# MSXII_DC-DC_Converter.net
KiCad netlist of a schematic drawn in Altium Designer
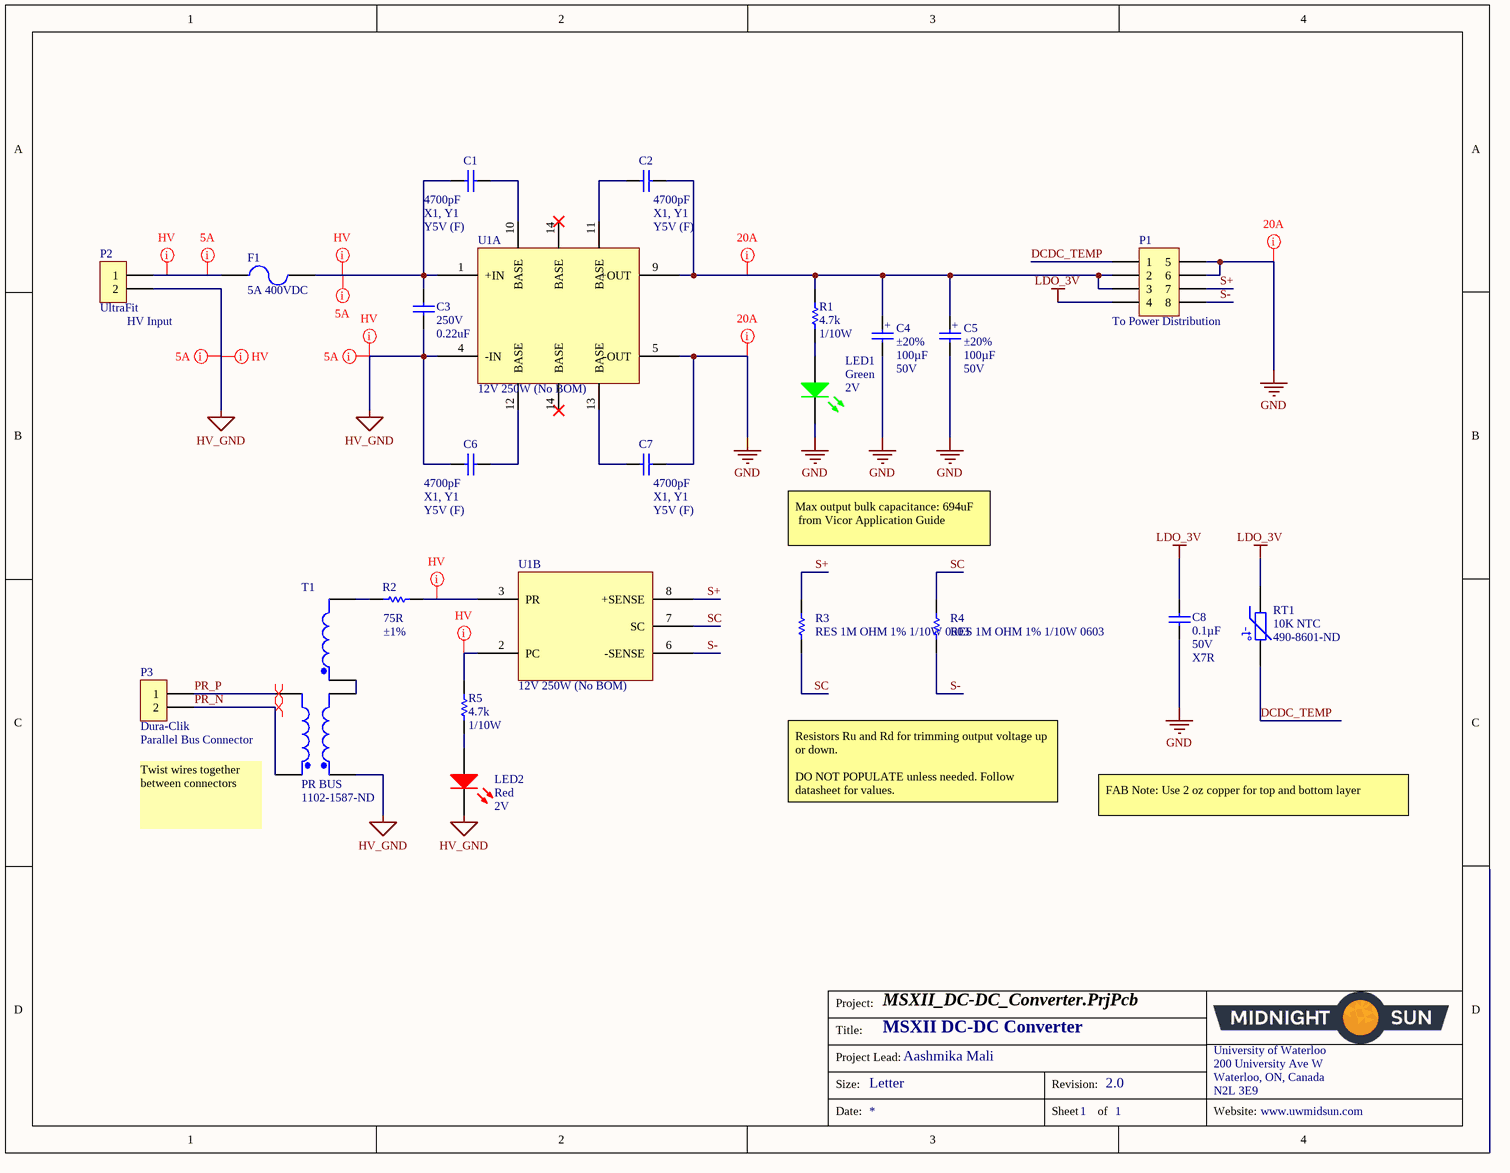
[diagram p0: MSXII_DC-DC_Converter.SchDoc]

(export (version "E")
  (design (tool "Eeschema 10.0.6"))
  (components
    (comp (ref "C1")
      (value "4700pF")
      (footprint "CAP 4700PF 400VAC Y5V RADIAL")
      (description "4700pF ±20% 400VAC Ceramic Capacitor Y5V (F) Radial, Disc")
      (fields
        (field (name "MANUFACTURER") "KEMET")
        (field (name "MANUFACTURER PART NUMBER") "C951U472MVVDBA7317")
        (field (name "TEMPERATURE COEFFICIENT") "Y5V (F)")
        (field (name "RATINGS") "X1, Y1")
      )
      (libsource (lib "Schematic Diagrams") (part "CAP CER 4700PF 400VAC Y5V RADIAL"))
    )
    (comp (ref "C2")
      (value "4700pF")
      (footprint "CAP 4700PF 400VAC Y5V RADIAL")
      (description "4700pF ±20% 400VAC Ceramic Capacitor Y5V (F) Radial, Disc")
      (fields
        (field (name "MANUFACTURER") "KEMET")
        (field (name "MANUFACTURER PART NUMBER") "C951U472MVVDBA7317")
        (field (name "TEMPERATURE COEFFICIENT") "Y5V (F)")
        (field (name "RATINGS") "X1, Y1")
      )
      (libsource (lib "Schematic Diagrams") (part "CAP CER 4700PF 400VAC Y5V RADIAL"))
    )
    (comp (ref "C3")
      (value "0.22uF")
      (footprint "CAP FILM 0.22UF 5% 250VDC RADIAL")
      (fields
        (field (name "MANUFACTURER") "KEMET")
        (field (name "MANUFACTURER PART NUMBER") "R82IC3220AA60J")
        (field (name "TOLERANCE") "±5%")
        (field (name "VOLTAGE RATING - DC") "250V")
      )
      (libsource (lib "Schematic Diagrams") (part "CAP FILM 0.22UF 5% 250VDC RADIAL"))
    )
    (comp (ref "C4")
      (value "CAP ALUM 100UF 20% 50V RADIAL")
      (footprint "CAP ALUM 100UF 50V")
      (description "100µF 50V Aluminum Capacitors Radial, Can 74 mOhm @ 100kHz 3000 Hrs @ 105°C")
      (fields
        (field (name "TOLERANCE") "±20%")
        (field (name "CAPACITANCE") "100µF")
        (field (name "VOLTAGE RATING") "50V")
      )
      (libsource (lib "Schematic Diagrams") (part "CAP ALUM 100UF 20% 50V RADIAL"))
    )
    (comp (ref "C5")
      (value "CAP ALUM 100UF 20% 50V RADIAL")
      (footprint "CAP ALUM 100UF 50V")
      (description "100µF 50V Aluminum Capacitors Radial, Can 74 mOhm @ 100kHz 3000 Hrs @ 105°C")
      (fields
        (field (name "TOLERANCE") "±20%")
        (field (name "CAPACITANCE") "100µF")
        (field (name "VOLTAGE RATING") "50V")
      )
      (libsource (lib "Schematic Diagrams") (part "CAP ALUM 100UF 20% 50V RADIAL"))
    )
    (comp (ref "C6")
      (value "4700pF")
      (footprint "CAP 4700PF 400VAC Y5V RADIAL")
      (description "4700pF ±20% 400VAC Ceramic Capacitor Y5V (F) Radial, Disc")
      (fields
        (field (name "MANUFACTURER") "KEMET")
        (field (name "MANUFACTURER PART NUMBER") "C951U472MVVDBA7317")
        (field (name "TEMPERATURE COEFFICIENT") "Y5V (F)")
        (field (name "RATINGS") "X1, Y1")
      )
      (libsource (lib "Schematic Diagrams") (part "CAP CER 4700PF 400VAC Y5V RADIAL"))
    )
    (comp (ref "C7")
      (value "4700pF")
      (footprint "CAP 4700PF 400VAC Y5V RADIAL")
      (description "4700pF ±20% 400VAC Ceramic Capacitor Y5V (F) Radial, Disc")
      (fields
        (field (name "MANUFACTURER") "KEMET")
        (field (name "MANUFACTURER PART NUMBER") "C951U472MVVDBA7317")
        (field (name "TEMPERATURE COEFFICIENT") "Y5V (F)")
        (field (name "RATINGS") "X1, Y1")
      )
      (libsource (lib "Schematic Diagrams") (part "CAP CER 4700PF 400VAC Y5V RADIAL"))
    )
    (comp (ref "C8")
      (value "CAP CER 0.1UF 50V 10% X7R 0603")
      (footprint "CAP, 0603")
      (description "0.10µF ±10% 50V Ceramic Capacitor X7R 0603 (1608 Metric)")
      (fields
        (field (name "TOLERANCE") "±10%")
        (field (name "CAPACITANCE") "0.1µF")
        (field (name "VOLTAGE") "50V")
        (field (name "TEMPERATURE COEFFICIENT") "X7R")
      )
      (libsource (lib "Schematic Diagrams") (part "CAP CER 0.1UF 50V 10% X7R 0603"))
    )
    (comp (ref "F1")
      (value "5A 400VDC")
      (footprint "FUSE 5A 400VDC RADIAL")
      (description "FUSE BOARD MNT 5A 125VAC/400VDC")
      (fields (field (name "MANUFACTURER") "Eaton") (field (name "MANUFACTURER PART NUMBER") "BK/PCE-5-R"))
      (libsource (lib "Schematic Diagrams") (part "FUSE 5A 125VAC/400VDC RADIAL"))
    )
    (comp (ref "LED1")
      (value "LED GREEN CLEAR 2V 0603")
      (footprint "LED_0603")
      (description "Green 572nm LED Indication - Discrete 2V 0603 (1608 Metric)")
      (fields
        (field (name "MANUFACTURER") "Wurth Electronics Inc.")
        (field (name "MANUFACTURER PART NUMBER") "150060VS75000")
        (field (name "COLOR") "Green")
        (field (name "VOLTAGE - FORWARD (VF) (TYP)") "2V")
      )
      (libsource (lib "Schematic Diagrams") (part "LED GREEN CLEAR 2V 0603"))
    )
    (comp (ref "LED2")
      (value "LED RED CLEAR 2V 0603")
      (footprint "LED_0603")
      (description "Red 631nm LED Indication - Discrete 2V 0603 (1608 Metric)")
      (fields
        (field (name "MANUFACTURER") "Wurth Electronics Inc.")
        (field (name "MANUFACTURER PART NUMBER") "150060RS75000")
        (field (name "COLOR") "Red")
        (field (name "VOLTAGE - FORWARD (VF) (TYP)") "2V")
      )
      (libsource (lib "Schematic Diagrams") (part "LED RED CLEAR 2V 0603"))
    )
    (comp (ref "P1")
      (value "CONN 8POS ULTRA-FIT 0.138\"")
      (footprint "CONN, 8POS ULTRA-FIT")
      (description "8 Positions Header Connector 0.138\" (3.50mm) Through Hole Tin")
      (fields
        (field (name "MANUFACTURER") "Molex, LLC")
        (field (name "MANUFACTURER PART NUMBER") "1722991108")
      )
      (libsource (lib "Schematic Diagrams") (part "CONN 8POS ULTRA-FIT 0.138{dblquote}"))
    )
    (comp (ref "P2")
      (value "CONN 2POS ULTRA-FIT 0.138\"")
      (footprint "CONN, 2POS ULTRA-FIT")
      (description "2 Positions Header, Shrouded Connector 0.138\" (3.50mm) Through Hole Gold")
      (fields (field (name "VOLTAGE") "400V") (field (name "SERIES") "UltraFit"))
      (libsource (lib "Schematic Diagrams") (part "CONN 2POS ULTRA-FIT 0.138{dblquote}"))
    )
    (comp (ref "P3")
      (value "Dura-Clik")
      (footprint "CONN, 2POS Dura-Click Vertical")
      (description "2 Positions Header, Shrouded Connector 0.079\" (2.00mm) Surface Mount, Vertical Tin")
      (fields
        (field (name "MANUFACTURER") "Molex, LLC")
        (field (name "MANUFACTURER PART NUMBER") "5600200220")
      )
      (libsource (lib "Schematic Diagrams") (part "CONN 2POS DURA-CLIK 0.079{dblquote} VERT"))
    )
    (comp (ref "R1")
      (value "RES 4.7K OHM 1% 1/10W 0603")
      (footprint "RES, 0603")
      (description "4.7k Ohm ±1% 0.1W, 1/10W Chip Resistor 0603 (1608 Metric) Moisture Resistant Thick Film")
      (fields
        (field (name "TOLERANCE") "±1%")
        (field (name "RESISTANCE (OHMS)") "4.7k")
        (field (name "POWER (WATTS)") "1/10W")
      )
      (libsource (lib "Schematic Diagrams") (part "RES 4.7K OHM 1% 1/10W 0603"))
    )
    (comp (ref "R2")
      (value "75R")
      (footprint "RES, 0603")
      (fields
        (field (name "MANUFACTURER") "Yageo")
        (field (name "MANUFACTURER PART NUMBER") "AC0603FR-0775RL")
        (field (name "TOLERANCE") "±1%")
        (field (name "Comment") "RES 75R OHM 1% 1/10W 0603")
      )
      (libsource (lib "Schematic Diagrams") (part "RES 75R OHM 1% 1/10W 0603"))
    )
    (comp (ref "R3")
      (value "RES 1M OHM 1% 1/10W 0603")
      (footprint "RES, 0603")
      (description "1M Ohm ±1% 0.1W, 1/10W Chip Resistor 0603 (1608 Metric) Moisture Resistant Thick Film")
      (fields (field (name "TOLERANCE") "±1%"))
      (libsource (lib "Schematic Diagrams") (part "RES 1M OHM 1% 1/10W 0603"))
    )
    (comp (ref "R4")
      (value "RES 1M OHM 1% 1/10W 0603")
      (footprint "RES, 0603")
      (description "1M Ohm ±1% 0.1W, 1/10W Chip Resistor 0603 (1608 Metric) Moisture Resistant Thick Film")
      (fields (field (name "TOLERANCE") "±1%"))
      (libsource (lib "Schematic Diagrams") (part "RES 1M OHM 1% 1/10W 0603"))
    )
    (comp (ref "R5")
      (value "RES 4.7K OHM 1% 1/10W 0603")
      (footprint "RES, 0603")
      (description "4.7k Ohm ±1% 0.1W, 1/10W Chip Resistor 0603 (1608 Metric) Moisture Resistant Thick Film")
      (fields
        (field (name "TOLERANCE") "±1%")
        (field (name "RESISTANCE (OHMS)") "4.7k")
        (field (name "POWER (WATTS)") "1/10W")
      )
      (libsource (lib "Schematic Diagrams") (part "RES 4.7K OHM 1% 1/10W 0603"))
    )
    (comp (ref "RT1")
      (value "10K NTC")
      (footprint "NTC THERMISTOR BEAD")
      (description "NTC Thermistor 10k Bead")
      (fields
        (field (name "MANUFACTURER") "Murata Electronics North America")
        (field (name "MANUFACTURER PART NUMBER") "NXRT15XH103FA1B030")
        (field (name "SUPPLIER PART NUMBER 1") "490-8601-ND")
      )
      (libsource (lib "Schematic Diagrams") (part "NTC THERMISTOR 10K 1% BEAD"))
    )
    (comp (ref "T1")
      (value "PR BUS")
      (footprint "XFMR PR BUS")
      (description "Transformer for PR bus on Vicor DC-DC")
      (fields
        (field (name "MANUFACTURER") "Vicor Corporation")
        (field (name "MANUFACTURER PART NUMBER") "29768")
        (field (name "SUPPLIER PART NUMBER 1") "1102-1587-ND")
      )
      (libsource (lib "Schematic Diagrams") (part "XFMR PR BUS"))
    )
    (comp (ref "U1")
      (value "12V 250W (No BOM)")
      (footprint "DCDC VICOR 150V-12V 250W")
      (description "Isolated Module DC DC Converter 1 Output 12V 20.83A 100V - 200V Input")
      (fields
        (field (name "MANUFACTURER") "Vicor Corporation")
        (field (name "MANUFACTURER PART NUMBER") "V150B12C250BL")
      )
      (libsource (lib "Schematic Diagrams") (part "DCDC VICOR 150V-12V 250W"))
    )
  )
  (nets
    (net (code "1") (name "/DCDC_TEMP") (class "Default")
      (node (ref "P1") (pin "1") (pinfunction "1_1") (pintype "passive"))
      (node (ref "RT1") (pin "2") (pinfunction "2_2") (pintype "passive"))
    )
    (net (code "2") (name "/PR_N") (class "Default")
      (node (ref "P3") (pin "2") (pinfunction "2_2") (pintype "passive"))
      (node (ref "T1") (pin "5") (pinfunction "Sec1+_5") (pintype "passive"))
    )
    (net (code "3") (name "/PR_P") (class "Default")
      (node (ref "P3") (pin "1") (pinfunction "1_1") (pintype "passive"))
      (node (ref "T1") (pin "6") (pinfunction "Sec1-_6") (pintype "passive"))
    )
    (net (code "4") (name "/S+") (class "Default")
      (node (ref "P1") (pin "7") (pinfunction "7_7") (pintype "passive"))
      (node (ref "R3") (pin "1") (pinfunction "1_1") (pintype "passive"))
      (node (ref "U1") (pin "8") (pinfunction "+SENSE_8") (pintype "passive"))
    )
    (net (code "5") (name "/S-") (class "Default")
      (node (ref "P1") (pin "8") (pinfunction "8_8") (pintype "passive"))
      (node (ref "R4") (pin "2") (pinfunction "2_2") (pintype "passive"))
      (node (ref "U1") (pin "6") (pinfunction "-SENSE_6") (pintype "passive"))
    )
    (net (code "6") (name "/SC") (class "Default")
      (node (ref "R3") (pin "2") (pinfunction "2_2") (pintype "passive"))
      (node (ref "R4") (pin "1") (pinfunction "1_1") (pintype "passive"))
      (node (ref "U1") (pin "7") (pinfunction "SC_7") (pintype "passive"))
    )
    (net (code "7") (name "GND") (class "Default")
      (node (ref "C4") (pin "2") (pinfunction "2_2") (pintype "passive"))
      (node (ref "C5") (pin "2") (pinfunction "2_2") (pintype "passive"))
      (node (ref "C7") (pin "2") (pinfunction "2_2") (pintype "passive"))
      (node (ref "C8") (pin "2") (pinfunction "2_2") (pintype "passive"))
      (node (ref "LED1") (pin "2") (pinfunction "K_2") (pintype "passive"))
      (node (ref "P1") (pin "5") (pinfunction "5_5") (pintype "passive"))
      (node (ref "P1") (pin "6") (pinfunction "6_6") (pintype "passive"))
      (node (ref "U1") (pin "5") (pinfunction "-OUT_5") (pintype "passive"))
    )
    (net (code "8") (name "HV_GND") (class "Default")
      (node (ref "C3") (pin "1") (pinfunction "1_1") (pintype "passive"))
      (node (ref "C6") (pin "1") (pinfunction "1_1") (pintype "passive"))
      (node (ref "LED2") (pin "2") (pinfunction "K_2") (pintype "passive"))
      (node (ref "P2") (pin "2") (pinfunction "2_2") (pintype "passive"))
      (node (ref "T1") (pin "1") (pinfunction "Pri+_1") (pintype "passive"))
      (node (ref "U1") (pin "4") (pinfunction "-IN_4") (pintype "passive"))
    )
    (net (code "9") (name "LDO_3V") (class "Default")
      (node (ref "C8") (pin "1") (pinfunction "1_1") (pintype "passive"))
      (node (ref "P1") (pin "4") (pinfunction "4_4") (pintype "passive"))
      (node (ref "RT1") (pin "1") (pinfunction "1_1") (pintype "passive"))
    )
    (net (code "10") (name "Net-(C1-Pad2)") (class "Default")
      (node (ref "C1") (pin "2") (pinfunction "2_2") (pintype "passive"))
      (node (ref "U1") (pin "10") (pinfunction "BASE_10") (pintype "passive"))
    )
    (net (code "11") (name "Net-(C2-Pad1)") (class "Default")
      (node (ref "C2") (pin "1") (pinfunction "1_1") (pintype "passive"))
      (node (ref "U1") (pin "11") (pinfunction "BASE_11") (pintype "passive"))
    )
    (net (code "12") (name "Net-(C6-Pad2)") (class "Default")
      (node (ref "C6") (pin "2") (pinfunction "2_2") (pintype "passive"))
      (node (ref "U1") (pin "12") (pinfunction "BASE_12") (pintype "passive"))
    )
    (net (code "13") (name "Net-(C7-Pad1)") (class "Default")
      (node (ref "C7") (pin "1") (pinfunction "1_1") (pintype "passive"))
      (node (ref "U1") (pin "13") (pinfunction "BASE_13") (pintype "passive"))
    )
    (net (code "14") (name "Net-(F1-Pad1)") (class "Default")
      (node (ref "F1") (pin "1") (pinfunction "1_1") (pintype "passive"))
      (node (ref "P2") (pin "1") (pinfunction "1_1") (pintype "passive"))
    )
    (net (code "15") (name "Net-(LED1-A)") (class "Default")
      (node (ref "LED1") (pin "1") (pinfunction "A_1") (pintype "passive"))
      (node (ref "R1") (pin "2") (pinfunction "2_2") (pintype "passive"))
    )
    (net (code "16") (name "Net-(LED2-A)") (class "Default")
      (node (ref "LED2") (pin "1") (pinfunction "A_1") (pintype "passive"))
      (node (ref "R5") (pin "2") (pinfunction "2_2") (pintype "passive"))
    )
    (net (code "17") (name "Net-(T1-Pri-)") (class "Default")
      (node (ref "T1") (pin "2") (pinfunction "Pri-_2") (pintype "passive"))
      (node (ref "T1") (pin "3") (pinfunction "Sec2+_3") (pintype "passive"))
    )
    (net (code "18") (name "Net-(T1-Sec2-)") (class "Default")
      (node (ref "R2") (pin "1") (pinfunction "1_1") (pintype "passive"))
      (node (ref "T1") (pin "4") (pinfunction "Sec2-_4") (pintype "passive"))
    )
    (net (code "19") (name "Net-(U1A-+IN)") (class "Default")
      (node (ref "C1") (pin "1") (pinfunction "1_1") (pintype "passive"))
      (node (ref "C3") (pin "2") (pinfunction "2_2") (pintype "passive"))
      (node (ref "F1") (pin "2") (pinfunction "2_2") (pintype "passive"))
      (node (ref "U1") (pin "1") (pinfunction "+IN_1") (pintype "passive"))
    )
    (net (code "20") (name "Net-(U1A-+OUT)") (class "Default")
      (node (ref "C2") (pin "2") (pinfunction "2_2") (pintype "passive"))
      (node (ref "C4") (pin "1") (pinfunction "1_1") (pintype "passive"))
      (node (ref "C5") (pin "1") (pinfunction "1_1") (pintype "passive"))
      (node (ref "P1") (pin "2") (pinfunction "2_2") (pintype "passive"))
      (node (ref "P1") (pin "3") (pinfunction "3_3") (pintype "passive"))
      (node (ref "R1") (pin "1") (pinfunction "1_1") (pintype "passive"))
      (node (ref "U1") (pin "9") (pinfunction "+OUT_9") (pintype "passive"))
    )
    (net (code "21") (name "Net-(U1B-PC)") (class "Default")
      (node (ref "R5") (pin "1") (pinfunction "1_1") (pintype "passive"))
      (node (ref "U1") (pin "2") (pinfunction "PC_2") (pintype "passive"))
    )
    (net (code "22") (name "Net-(U1B-PR)") (class "Default")
      (node (ref "R2") (pin "2") (pinfunction "2_2") (pintype "passive"))
      (node (ref "U1") (pin "3") (pinfunction "PR_3") (pintype "passive"))
    )
    (net (code "23") (name "unconnected-(U1A-BASE-Pad14)") (class "Default")
      (node (ref "U1") (pin "14") (pinfunction "BASE_14") (pintype "passive+no_connect"))
    )
    (net (code "24") (name "unconnected-(U1A-BASE-Pad14)_1") (class "Default")
      (node (ref "U1") (pin "14") (pinfunction "BASE_14") (pintype "passive+no_connect"))
    )
  )
)
